# Sheet1.net
KiCad netlist of a schematic drawn in Altium Designer
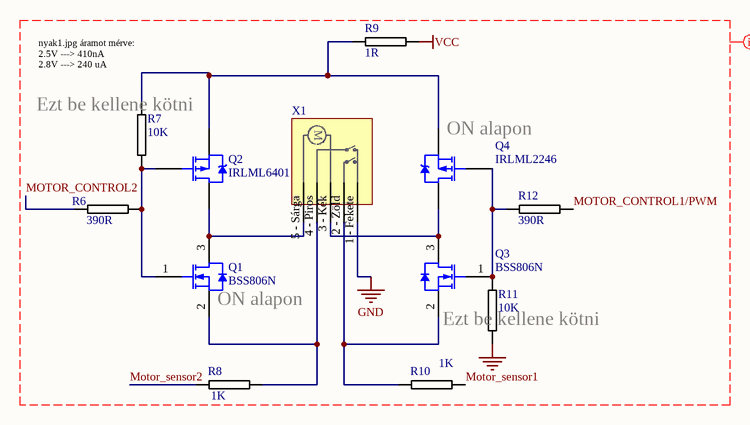
[diagram p0: Sheet1.SchDoc]

(export (version "E")
  (design (tool "Eeschema 10.0.6"))
  (components
    (comp (ref "Q1")
      (value "BSS806N")
      (footprint "INF-PG-SOT23_N")
      (fields (field (name "MANUFACTURER") "Infineon"))
      (libsource (lib "Infineon_Power_MOSFET") (part "BSS806N"))
    )
    (comp (ref "Q2")
      (value "IRLML6401")
      (footprint "Micro3_N")
      (description "HEXFET Power MOSFET")
      (fields (field (name "PUBLISHER") "Altium Limited"))
      (libsource (lib "IR Discrete MOSFET - Power") (part "IRLML6401"))
    )
    (comp (ref "Q3")
      (value "BSS806N")
      (footprint "INF-PG-SOT23_N")
      (fields (field (name "MANUFACTURER") "Infineon"))
      (libsource (lib "Infineon_Power_MOSFET") (part "BSS806N"))
    )
    (comp (ref "Q4")
      (value "IRLML2246")
      (footprint "Micro3_N")
      (description "HEXFET Power MOSFET")
      (fields (field (name "PUBLISHER") "Altium Limited"))
      (libsource (lib "IR Discrete MOSFET - Power") (part "IRLML6401"))
    )
    (comp (ref "R6")
      (value "390R")
      (footprint "0805R-390")
      (description "RESISTOR 0805 1/4 WATT THIN FILM")
      (libsource (lib "vh_altium_library") (part "0805R-390"))
    )
    (comp (ref "R7")
      (value "10K")
      (footprint "0805R-10K")
      (description "RESISTOR 0805 1/4 WATT THIN FILM")
      (libsource (lib "vh_altium_library") (part "0805R-10K"))
    )
    (comp (ref "R8")
      (value "1K")
      (footprint "0805R-1K")
      (description "RESISTOR 0805 1/4 WATT THIN FILM")
      (libsource (lib "vh_altium_library") (part "0805R-1K"))
    )
    (comp (ref "R9")
      (value "1R")
      (footprint "1206FB-50Z")
      (description "RESISTOR 0805 1/3 WATT")
      (libsource (lib "vh_altium_library") (part "0805R-1R"))
    )
    (comp (ref "R10")
      (value "1K")
      (footprint "0805R-1K")
      (description "RESISTOR 0805 1/4 WATT THIN FILM")
      (libsource (lib "vh_altium_library") (part "0805R-1K"))
    )
    (comp (ref "R11")
      (value "10K")
      (footprint "0805R-10K")
      (description "RESISTOR 0805 1/4 WATT THIN FILM")
      (libsource (lib "vh_altium_library") (part "0805R-10K"))
    )
    (comp (ref "R12")
      (value "390R")
      (footprint "0805R-390")
      (description "RESISTOR 0805 1/4 WATT THIN FILM")
      (libsource (lib "vh_altium_library") (part "0805R-390"))
    )
    (comp (ref "X1")
      (value "Component_1")
      (footprint "Szelep_csati")
      (libsource (lib "components") (part "szelep_csati1"))
    )
  )
  (nets
    (net (code "1") (name "/MOTOR_CONTROL1{slash}PWM") (class "Default")
      (node (ref "R12") (pin "2") (pintype "passive"))
    )
    (net (code "2") (name "/MOTOR_CONTROL2") (class "Default")
      (node (ref "R6") (pin "1") (pintype "passive"))
    )
    (net (code "3") (name "/Motor_sensor1") (class "Default")
      (node (ref "R10") (pin "2") (pintype "passive"))
    )
    (net (code "4") (name "/Motor_sensor2") (class "Default") (node (ref "R8") (pin "1") (pintype "passive")))
    (net (code "5") (name "GND") (class "Default")
      (node (ref "R11") (pin "2") (pintype "passive"))
      (node (ref "X1") (pin "1_-_Fekete") (pinfunction "1_1_-_Fekete") (pintype "passive"))
    )
    (net (code "6") (name "Net-(Q1-DRAIN)") (class "Default")
      (node (ref "Q1") (pin "3") (pinfunction "DRAIN_3") (pintype "passive"))
      (node (ref "Q2") (pin "3") (pinfunction "D_3") (pintype "passive"))
      (node (ref "X1") (pin "5_-_Sárga") (pinfunction "5_5_-_Sárga") (pintype "passive"))
    )
    (net (code "7") (name "Net-(Q1-GATE)") (class "Default")
      (node (ref "Q1") (pin "1") (pinfunction "GATE_1") (pintype "passive"))
      (node (ref "Q2") (pin "1") (pinfunction "G_1") (pintype "passive"))
      (node (ref "R6") (pin "2") (pintype "passive"))
      (node (ref "R7") (pin "2") (pintype "passive"))
    )
    (net (code "8") (name "Net-(Q1-SOURCE)") (class "Default")
      (node (ref "Q1") (pin "2") (pinfunction "SOURCE_2") (pintype "passive"))
      (node (ref "R8") (pin "2") (pintype "passive"))
      (node (ref "X1") (pin "4_-_Piros") (pinfunction "4_4_-_Piros") (pintype "passive"))
    )
    (net (code "9") (name "Net-(Q2-S)") (class "Default")
      (node (ref "Q2") (pin "2") (pinfunction "S_2") (pintype "passive"))
      (node (ref "Q4") (pin "2") (pinfunction "S_2") (pintype "passive"))
      (node (ref "R7") (pin "1") (pintype "passive"))
      (node (ref "R9") (pin "1") (pintype "passive"))
    )
    (net (code "10") (name "Net-(Q3-DRAIN)") (class "Default")
      (node (ref "Q3") (pin "3") (pinfunction "DRAIN_3") (pintype "passive"))
      (node (ref "Q4") (pin "3") (pinfunction "D_3") (pintype "passive"))
      (node (ref "X1") (pin "3_-_Kék") (pinfunction "3_3_-_Kék") (pintype "passive"))
    )
    (net (code "11") (name "Net-(Q3-GATE)") (class "Default")
      (node (ref "Q3") (pin "1") (pinfunction "GATE_1") (pintype "passive"))
      (node (ref "Q4") (pin "1") (pinfunction "G_1") (pintype "passive"))
      (node (ref "R11") (pin "1") (pintype "passive"))
      (node (ref "R12") (pin "1") (pintype "passive"))
    )
    (net (code "12") (name "Net-(Q3-SOURCE)") (class "Default")
      (node (ref "Q3") (pin "2") (pinfunction "SOURCE_2") (pintype "passive"))
      (node (ref "R10") (pin "1") (pintype "passive"))
      (node (ref "X1") (pin "2_-_Zöld") (pinfunction "2_2_-_Zöld") (pintype "passive"))
    )
    (net (code "13") (name "VCC") (class "Default") (node (ref "R9") (pin "2") (pintype "passive")))
  )
)
